# SensWear_PPG.net
KiCad netlist of a schematic drawn in Altium Designer
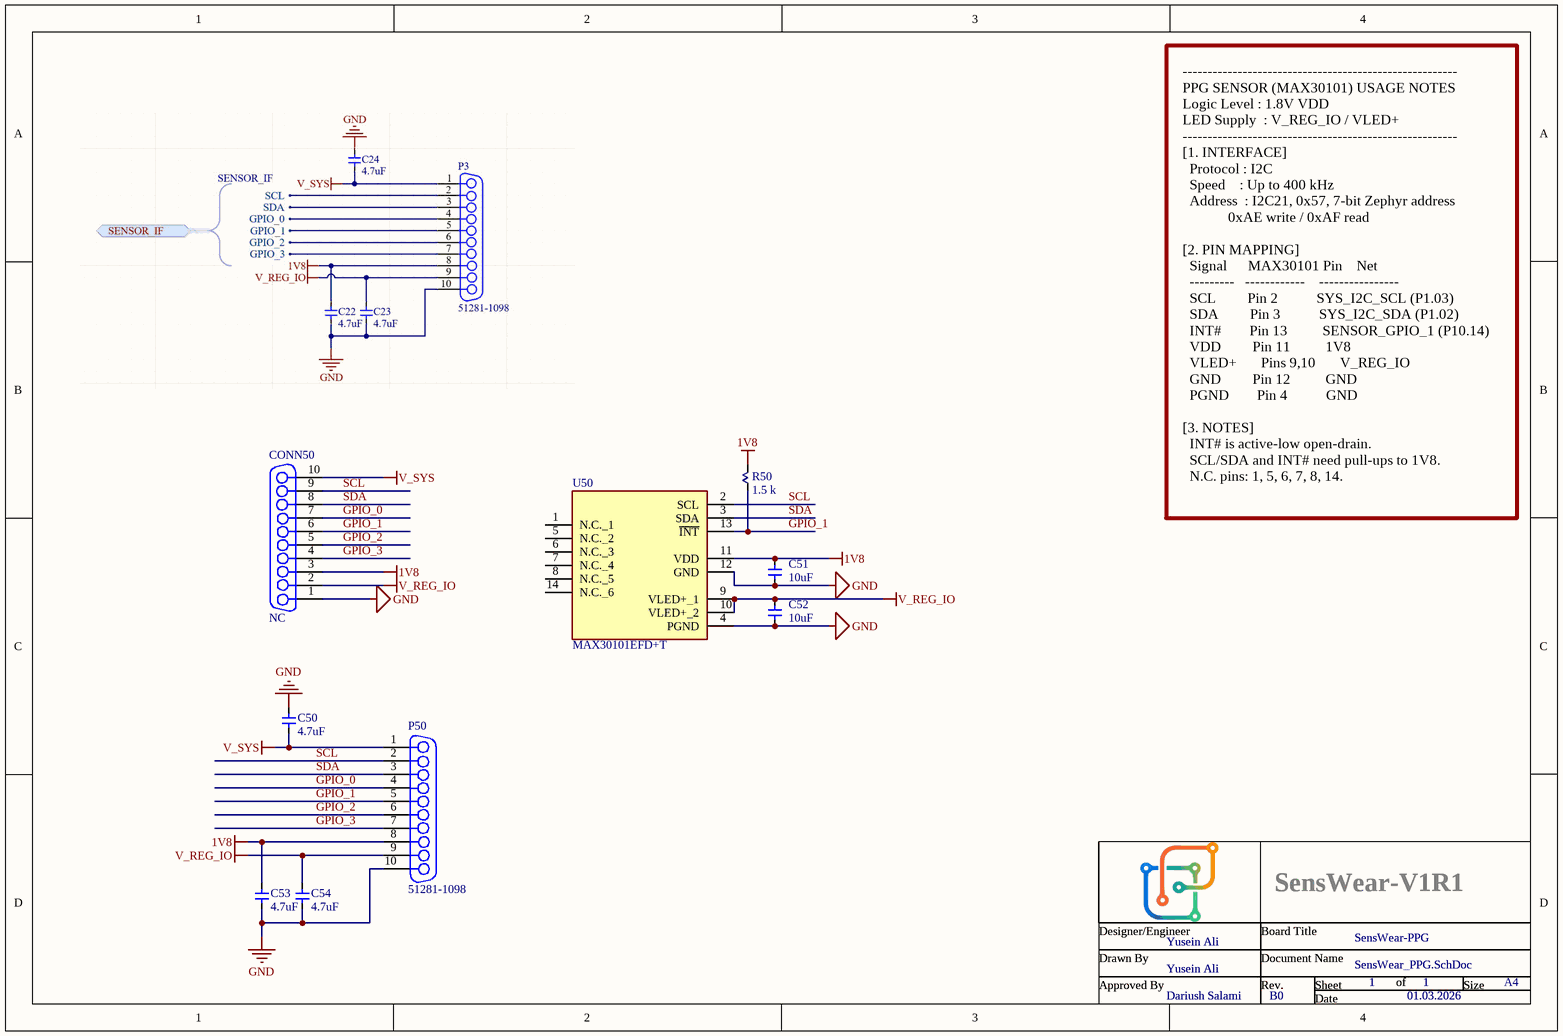
[diagram p0: SensWear_PPG.SchDoc]

(export (version "E")
  (design (tool "Eeschema 10.0.6"))
  (components
    (comp (ref "C50")
      (value "4.7uF")
      (footprint "CAPC1005X05N")
      (description "Multilayer Ceramic Capacitor, 4.7 uF, 10 V, ± 20%, X5R, 0402 [1005 Metric]")
      (fields
        (field (name "MANUFACTURER") "Murata")
        (field (name "MANUFACTURER PART NUMBER") "GRM155R61A475MEAAD")
      )
      (libsource (lib "SensWearComponents") (part "GRM155R61A475MEAAD__2"))
    )
    (comp (ref "C51")
      (value "10uF")
      (footprint "CAPC1005X05N")
      (description "Multilayer Ceramic Capacitor, 10 uF, 10 V, ± 20%, X5R, 0402 [1005 Metric]")
      (fields
        (field (name "MANUFACTURER") "Samsung")
        (field (name "MANUFACTURER PART NUMBER") "CL05A106MP5NUNC")
      )
      (libsource (lib "SensWearComponents") (part "CL05A106MP5NUNC"))
    )
    (comp (ref "C52")
      (value "10uF")
      (footprint "CAPC1005X05N")
      (description "Multilayer Ceramic Capacitor, 10 uF, 10 V, ± 20%, X5R, 0402 [1005 Metric]")
      (fields
        (field (name "MANUFACTURER") "Samsung")
        (field (name "MANUFACTURER PART NUMBER") "CL05A106MP5NUNC")
      )
      (libsource (lib "SensWearComponents") (part "CL05A106MP5NUNC"))
    )
    (comp (ref "C53")
      (value "4.7uF")
      (footprint "CAPC1005X05N")
      (description "Multilayer Ceramic Capacitor, 4.7 uF, 10 V, ± 20%, X5R, 0402 [1005 Metric]")
      (fields
        (field (name "MANUFACTURER") "Murata")
        (field (name "MANUFACTURER PART NUMBER") "GRM155R61A475MEAAD")
      )
      (libsource (lib "SensWearComponents") (part "GRM155R61A475MEAAD__2"))
    )
    (comp (ref "C54")
      (value "4.7uF")
      (footprint "CAPC1005X05N")
      (description "Multilayer Ceramic Capacitor, 4.7 uF, 10 V, ± 20%, X5R, 0402 [1005 Metric]")
      (fields
        (field (name "MANUFACTURER") "Murata")
        (field (name "MANUFACTURER PART NUMBER") "GRM155R61A475MEAAD")
      )
      (libsource (lib "SensWearComponents") (part "GRM155R61A475MEAAD__2"))
    )
    (comp (ref "CONN50")
      (value "NC")
      (footprint "51281-1098-PCB")
      (libsource (lib "SensWearComponents") (part "51281-1098-PCB__2"))
    )
    (comp (ref "P50")
      (value "51281-1098")
      (footprint "51281-1098__3")
      (description "FFC/FPC Connector, Surface Mount, Right-Angle, Non-ZIF, Dual Contact Style")
      (fields (field (name "MANUFACTURER") "Molex"))
      (libsource (lib "SensWearComponents") (part "51281-1098"))
    )
    (comp (ref "R50")
      (value "1.5 k")
      (footprint "RESC1005X04N")
      (description "RES SMD 1.5K OHM 1% 1/10W 0402")
      (fields
        (field (name "MANUFACTURER") "Panasonic Electronic Components")
        (field (name "MANUFACTURER PART NUMBER") "ERJ-2RKF1501X")
      )
      (libsource (lib "SensWearComponents") (part "ERJ-2RKF1501X"))
    )
    (comp (ref "U50")
      (value "MAX30101EFD+T")
      (footprint "14-LEAD-OESIP")
      (description "High-Sensitivity Pulse Oximeter and Heart-Rate Sensor for Fitness & Healthcare")
      (fields (field (name "MANUFACTURER") "Maxim"))
      (libsource (lib "SensWearComponents") (part "MAX30101EFD+T"))
    )
  )
  (nets
    (net (code "1") (name "/GPIO_0") (class "Default")
      (node (ref "CONN50") (pin "7") (pinfunction "7_7") (pintype "passive"))
      (node (ref "P50") (pin "4") (pinfunction "4_4") (pintype "passive"))
    )
    (net (code "2") (name "/GPIO_1") (class "Default")
      (node (ref "CONN50") (pin "6") (pinfunction "6_6") (pintype "passive"))
      (node (ref "P50") (pin "5") (pinfunction "5_5") (pintype "passive"))
      (node (ref "R50") (pin "1") (pinfunction "1_1") (pintype "passive"))
      (node (ref "U50") (pin "13") (pinfunction "~{INT}_13") (pintype "passive"))
    )
    (net (code "3") (name "/GPIO_2") (class "Default")
      (node (ref "CONN50") (pin "5") (pinfunction "5_5") (pintype "passive"))
      (node (ref "P50") (pin "6") (pinfunction "6_6") (pintype "passive"))
    )
    (net (code "4") (name "/GPIO_3") (class "Default")
      (node (ref "CONN50") (pin "4") (pinfunction "4_4") (pintype "passive"))
      (node (ref "P50") (pin "7") (pinfunction "7_7") (pintype "passive"))
    )
    (net (code "5") (name "/SCL") (class "Default")
      (node (ref "CONN50") (pin "9") (pinfunction "9_9") (pintype "passive"))
      (node (ref "P50") (pin "2") (pinfunction "2_2") (pintype "passive"))
      (node (ref "U50") (pin "2") (pinfunction "SCL_2") (pintype "passive"))
    )
    (net (code "6") (name "/SDA") (class "Default")
      (node (ref "CONN50") (pin "8") (pinfunction "8_8") (pintype "passive"))
      (node (ref "P50") (pin "3") (pinfunction "3_3") (pintype "passive"))
      (node (ref "U50") (pin "3") (pinfunction "SDA_3") (pintype "passive"))
    )
    (net (code "7") (name "1V8") (class "Default")
      (node (ref "C51") (pin "2") (pinfunction "2_2") (pintype "passive"))
      (node (ref "C53") (pin "2") (pinfunction "2_2") (pintype "passive"))
      (node (ref "CONN50") (pin "3") (pinfunction "3_3") (pintype "passive"))
      (node (ref "P50") (pin "8") (pinfunction "8_8") (pintype "passive"))
      (node (ref "R50") (pin "2") (pinfunction "2_2") (pintype "passive"))
      (node (ref "U50") (pin "11") (pinfunction "VDD_11") (pintype "passive"))
    )
    (net (code "8") (name "GND") (class "Default")
      (node (ref "C50") (pin "2") (pinfunction "2_2") (pintype "passive"))
      (node (ref "C51") (pin "1") (pinfunction "1_1") (pintype "passive"))
      (node (ref "C52") (pin "2") (pinfunction "2_2") (pintype "passive"))
      (node (ref "C53") (pin "1") (pinfunction "1_1") (pintype "passive"))
      (node (ref "C54") (pin "1") (pinfunction "1_1") (pintype "passive"))
      (node (ref "CONN50") (pin "1") (pinfunction "1_1") (pintype "passive"))
      (node (ref "P50") (pin "10") (pinfunction "10_10") (pintype "passive"))
      (node (ref "U50") (pin "12") (pinfunction "GND_12") (pintype "passive"))
      (node (ref "U50") (pin "4") (pinfunction "PGND_4") (pintype "passive"))
    )
    (net (code "9") (name "V_REG_IO") (class "Default")
      (node (ref "C52") (pin "1") (pinfunction "1_1") (pintype "passive"))
      (node (ref "C54") (pin "2") (pinfunction "2_2") (pintype "passive"))
      (node (ref "CONN50") (pin "2") (pinfunction "2_2") (pintype "passive"))
      (node (ref "P50") (pin "9") (pinfunction "9_9") (pintype "passive"))
      (node (ref "U50") (pin "10") (pinfunction "VLED+_2_10") (pintype "passive"))
      (node (ref "U50") (pin "9") (pinfunction "VLED+_1_9") (pintype "passive"))
    )
    (net (code "10") (name "V_SYS") (class "Default")
      (node (ref "C50") (pin "1") (pinfunction "1_1") (pintype "passive"))
      (node (ref "CONN50") (pin "10") (pinfunction "10_10") (pintype "passive"))
      (node (ref "P50") (pin "1") (pinfunction "1_1") (pintype "passive"))
    )
    (net (code "11") (name "unconnected-(U50-N.C._1-Pad1)") (class "Default")
      (node (ref "U50") (pin "1") (pinfunction "N.C._1_1") (pintype "passive"))
    )
    (net (code "12") (name "unconnected-(U50-N.C._2-Pad5)") (class "Default")
      (node (ref "U50") (pin "5") (pinfunction "N.C._2_5") (pintype "passive"))
    )
    (net (code "13") (name "unconnected-(U50-N.C._3-Pad6)") (class "Default")
      (node (ref "U50") (pin "6") (pinfunction "N.C._3_6") (pintype "passive"))
    )
    (net (code "14") (name "unconnected-(U50-N.C._4-Pad7)") (class "Default")
      (node (ref "U50") (pin "7") (pinfunction "N.C._4_7") (pintype "passive"))
    )
    (net (code "15") (name "unconnected-(U50-N.C._5-Pad8)") (class "Default")
      (node (ref "U50") (pin "8") (pinfunction "N.C._5_8") (pintype "passive"))
    )
    (net (code "16") (name "unconnected-(U50-N.C._6-Pad14)") (class "Default")
      (node (ref "U50") (pin "14") (pinfunction "N.C._6_14") (pintype "passive"))
    )
  )
)
